# Exercise_Sheet1.net
KiCad netlist of a schematic drawn in EAGLE
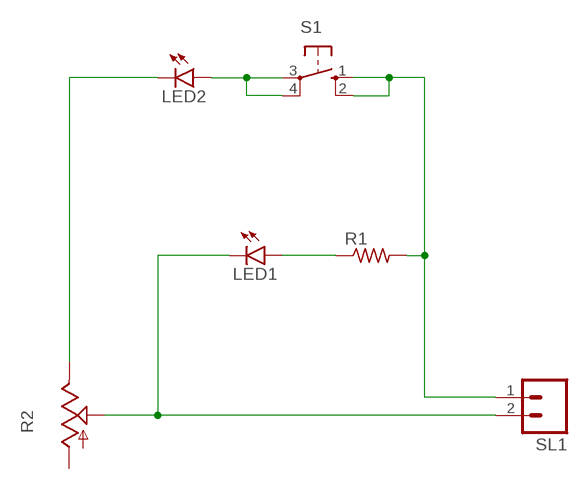
[diagram p0: schematic, sheet 1]

(export (version "E")
  (design (tool "Eeschema 10.0.6"))
  (components
    (comp (ref "LED1")
      (value "LED5MM")
      (footprint "eagle-import:LED5MM")
      (libsource (lib "eagle-import") (part "LED5MM"))
    )
    (comp (ref "LED2")
      (value "LED5MM")
      (footprint "eagle-import:LED5MM")
      (libsource (lib "eagle-import") (part "LED5MM"))
    )
    (comp (ref "R1")
      (value "R-US_0207/12")
      (footprint "eagle-import:0207_12")
      (libsource (lib "eagle-import") (part "R-US_0207/12"))
    )
    (comp (ref "R2")
      (value "TRIM_US-3223G")
      (footprint "eagle-import:3223G")
      (libsource (lib "eagle-import") (part "TRIM_US-3223G"))
    )
    (comp (ref "S1")
      (value "10-XX")
      (footprint "eagle-import:B3F-10XX")
      (fields (field (name "MPN") "B3F-1000"))
      (libsource (lib "eagle-import") (part "10-XX"))
    )
    (comp (ref "SL1")
      (value "M02")
      (footprint "eagle-import:02P")
      (libsource (lib "eagle-import") (part "M02"))
    )
  )
  (nets
    (net (code "1") (name "Net-(LED1-C)") (class "Default")
      (node (ref "LED1") (pin "K") (pinfunction "C_K") (pintype "passive"))
      (node (ref "R2") (pin "2") (pinfunction "S_2") (pintype "passive"))
      (node (ref "SL1") (pin "2") (pinfunction "2_2") (pintype "passive"))
    )
    (net (code "2") (name "Net-(LED1-PadA)") (class "Default")
      (node (ref "LED1") (pin "A") (pinfunction "A_A") (pintype "passive"))
      (node (ref "R1") (pin "1") (pinfunction "1_1") (pintype "passive"))
    )
    (net (code "3") (name "Net-(LED2-C)") (class "Default")
      (node (ref "LED2") (pin "K") (pinfunction "C_K") (pintype "passive"))
      (node (ref "R2") (pin "3") (pinfunction "E_3") (pintype "passive"))
    )
    (net (code "4") (name "Net-(S1-P)") (class "Default")
      (node (ref "LED2") (pin "A") (pinfunction "A_A") (pintype "passive"))
      (node (ref "S1") (pin "3") (pinfunction "P_3") (pintype "passive"))
      (node (ref "S1") (pin "4") (pinfunction "P1_4") (pintype "passive"))
    )
    (net (code "5") (name "Net-(S1-S)") (class "Default")
      (node (ref "R1") (pin "2") (pinfunction "2_2") (pintype "passive"))
      (node (ref "S1") (pin "1") (pinfunction "S_1") (pintype "passive"))
      (node (ref "S1") (pin "2") (pinfunction "S1_2") (pintype "passive"))
      (node (ref "SL1") (pin "1") (pinfunction "1_1") (pintype "passive"))
    )
    (net (code "6") (name "unconnected-(R2-A-Pad1)") (class "Default")
      (node (ref "R2") (pin "1") (pinfunction "A_1") (pintype "passive"))
    )
  )
)
